# atmega8_bk.net
KiCad netlist of a schematic drawn in EAGLE
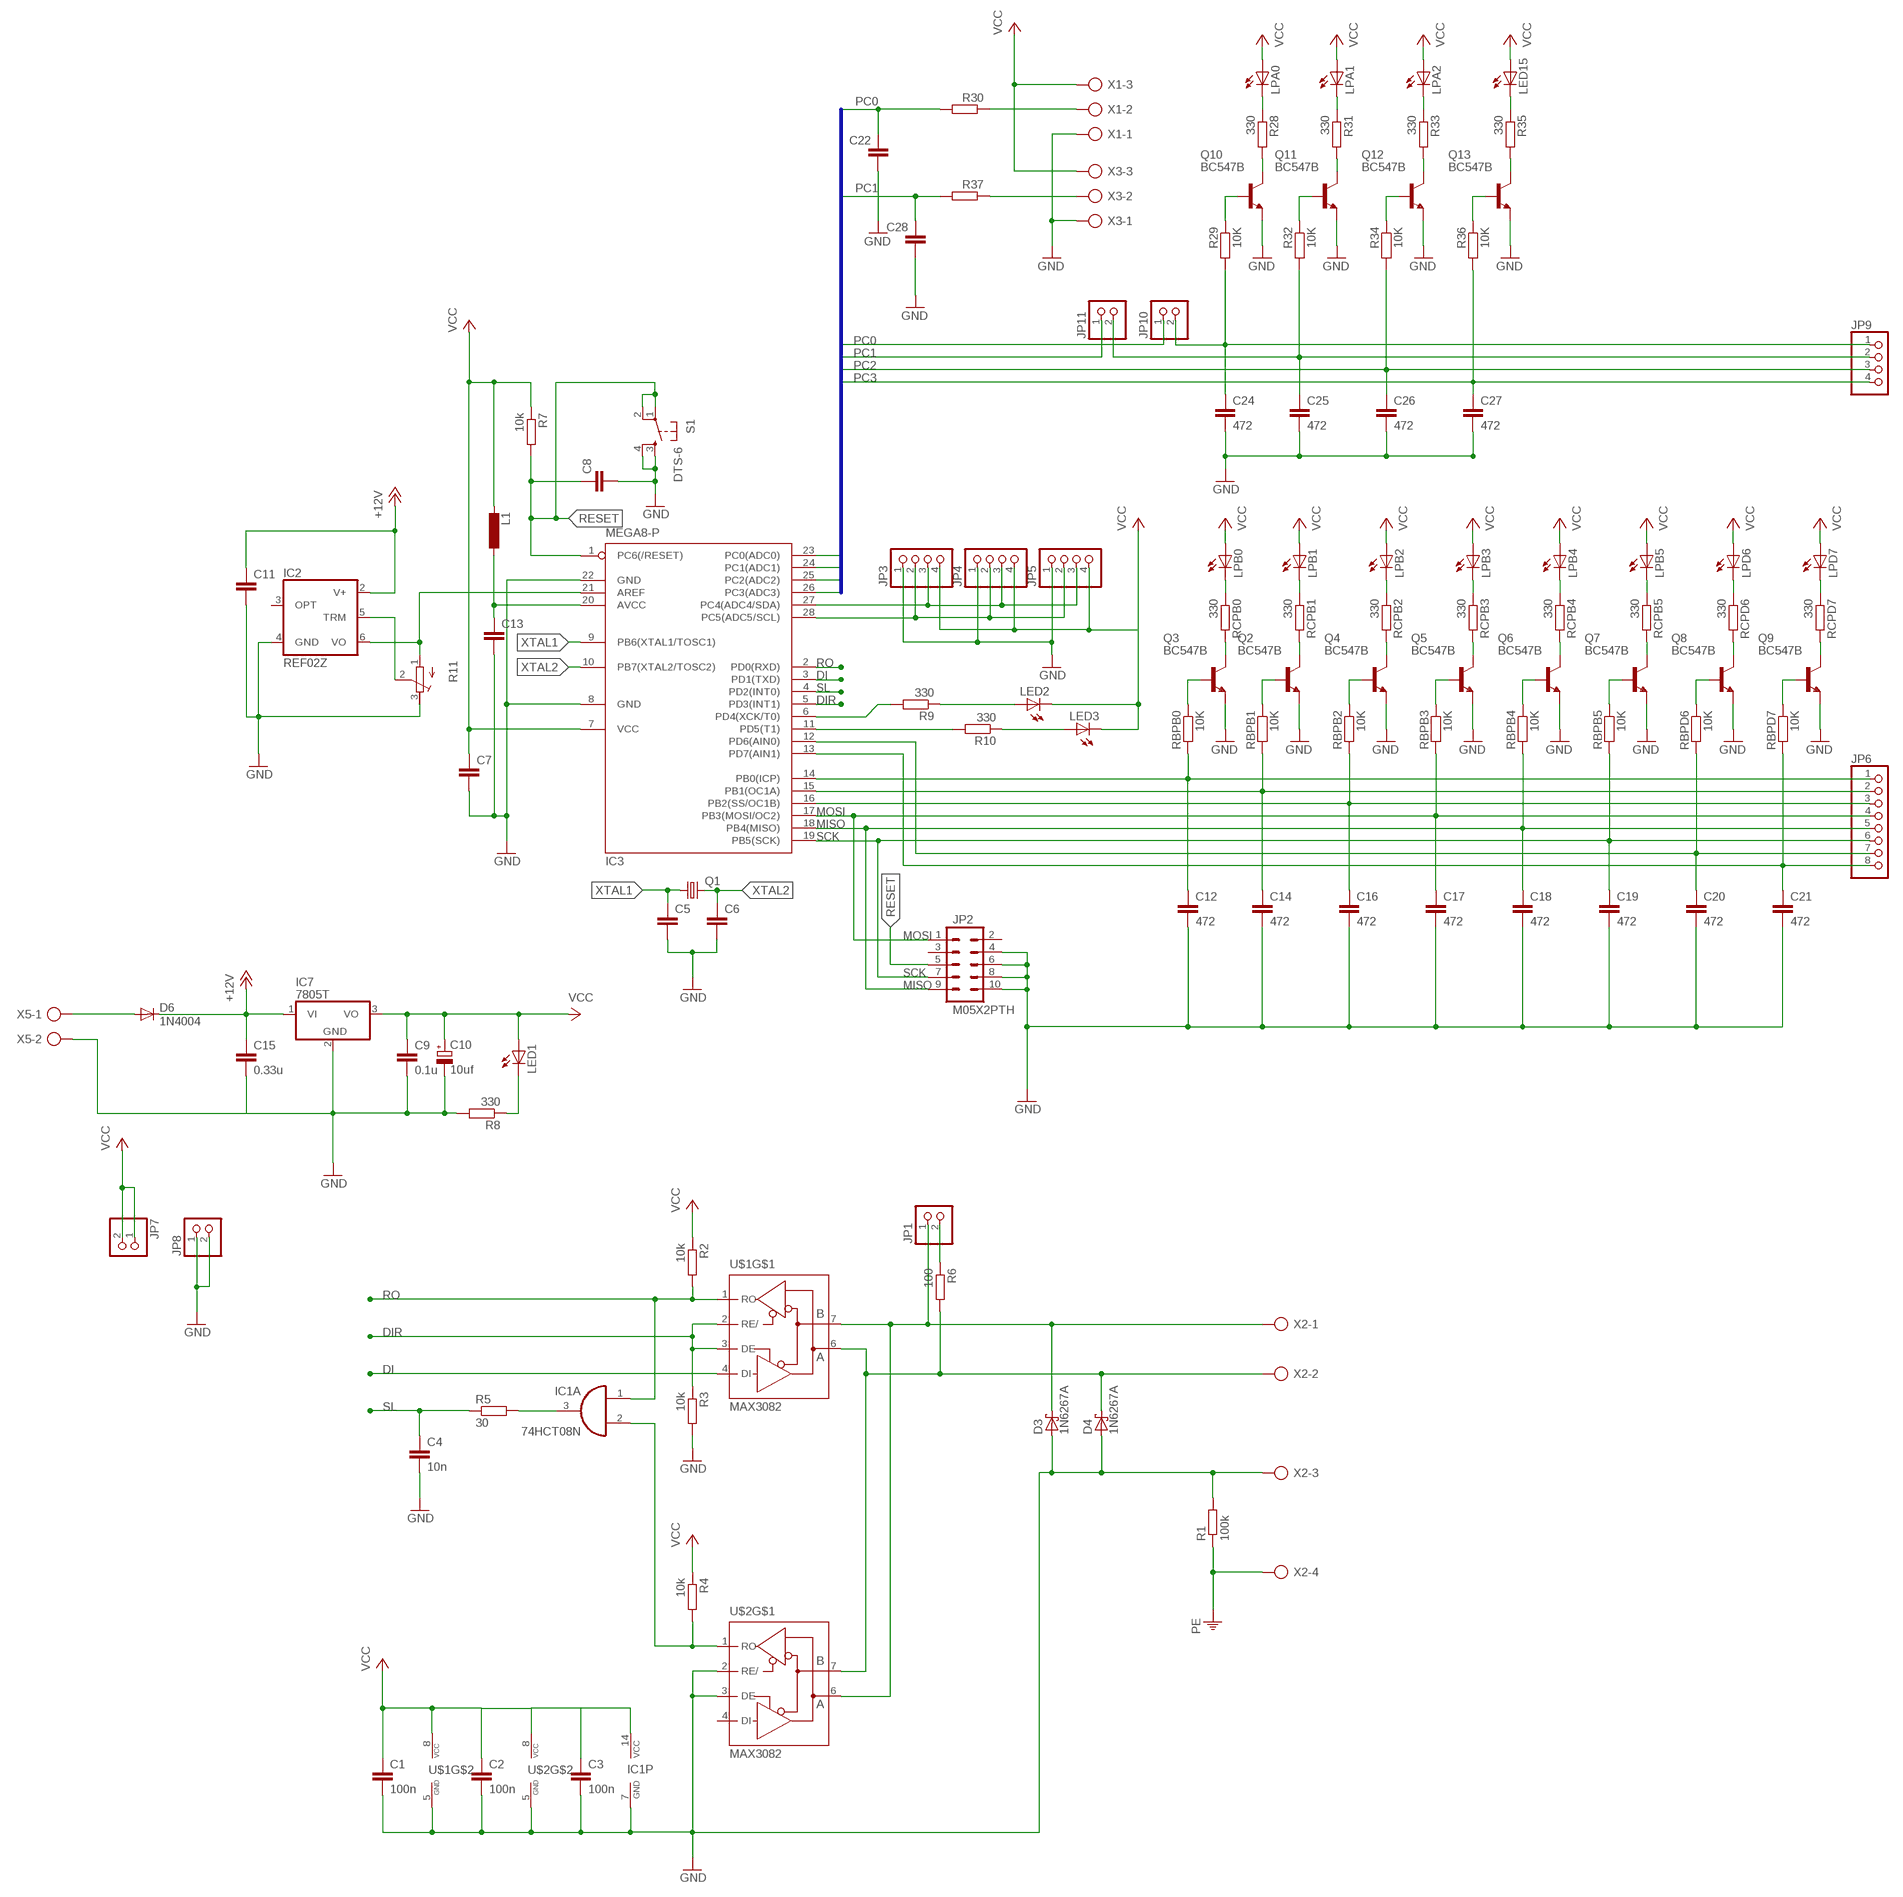
[diagram p0: schematic, sheet 1]

(export (version "E")
  (design (tool "Eeschema 10.0.6"))
  (components
    (comp (ref "C1")
      (value "100n")
      (footprint "eagle-import:C050-035X075")
      (libsource (lib "eagle-import") (part "C-EU050-035X075"))
    )
    (comp (ref "C2")
      (value "100n")
      (footprint "eagle-import:C050-035X075")
      (libsource (lib "eagle-import") (part "C-EU050-035X075"))
    )
    (comp (ref "C3")
      (value "100n")
      (footprint "eagle-import:C050-035X075")
      (libsource (lib "eagle-import") (part "C-EU050-035X075"))
    )
    (comp (ref "C4")
      (value "10n")
      (footprint "eagle-import:C050-035X075")
      (libsource (lib "eagle-import") (part "C-EU050-035X075"))
    )
    (comp (ref "C5")
      (value "C-EU050-024X044")
      (footprint "eagle-import:C050-024X044")
      (libsource (lib "eagle-import") (part "C-EU050-024X044"))
    )
    (comp (ref "C6")
      (value "C-EU050-024X044")
      (footprint "eagle-import:C050-024X044")
      (libsource (lib "eagle-import") (part "C-EU050-024X044"))
    )
    (comp (ref "C7")
      (value "C-EU050-025X075")
      (footprint "eagle-import:C050-025X075")
      (libsource (lib "eagle-import") (part "C-EU050-025X075"))
    )
    (comp (ref "C8")
      (value "C-EU050-025X075")
      (footprint "eagle-import:C050-025X075")
      (libsource (lib "eagle-import") (part "C-EU050-025X075"))
    )
    (comp (ref "C9")
      (value "0.1u")
      (footprint "eagle-import:C025-024X044")
      (libsource (lib "eagle-import") (part "C-EU025-024X044"))
    )
    (comp (ref "C10")
      (value "10uf")
      (footprint "eagle-import:E2-4")
      (libsource (lib "eagle-import") (part "CPOL-EUE2-4"))
    )
    (comp (ref "C11")
      (value "C-EU050-025X075")
      (footprint "eagle-import:C050-025X075")
      (libsource (lib "eagle-import") (part "C-EU050-025X075"))
    )
    (comp (ref "C12")
      (value "472")
      (footprint "eagle-import:C050-024X044")
      (libsource (lib "eagle-import") (part "C-EU050-024X044"))
    )
    (comp (ref "C13")
      (value "C-EU050-025X075")
      (footprint "eagle-import:C050-025X075")
      (libsource (lib "eagle-import") (part "C-EU050-025X075"))
    )
    (comp (ref "C14")
      (value "472")
      (footprint "eagle-import:C050-024X044")
      (libsource (lib "eagle-import") (part "C-EU050-024X044"))
    )
    (comp (ref "C15")
      (value "0.33u")
      (footprint "eagle-import:C025-024X044")
      (libsource (lib "eagle-import") (part "C-EU025-024X044"))
    )
    (comp (ref "C16")
      (value "472")
      (footprint "eagle-import:C050-024X044")
      (libsource (lib "eagle-import") (part "C-EU050-024X044"))
    )
    (comp (ref "C17")
      (value "472")
      (footprint "eagle-import:C050-024X044")
      (libsource (lib "eagle-import") (part "C-EU050-024X044"))
    )
    (comp (ref "C18")
      (value "472")
      (footprint "eagle-import:C050-024X044")
      (libsource (lib "eagle-import") (part "C-EU050-024X044"))
    )
    (comp (ref "C19")
      (value "472")
      (footprint "eagle-import:C050-024X044")
      (libsource (lib "eagle-import") (part "C-EU050-024X044"))
    )
    (comp (ref "C20")
      (value "472")
      (footprint "eagle-import:C050-024X044")
      (libsource (lib "eagle-import") (part "C-EU050-024X044"))
    )
    (comp (ref "C21")
      (value "472")
      (footprint "eagle-import:C050-024X044")
      (libsource (lib "eagle-import") (part "C-EU050-024X044"))
    )
    (comp (ref "C22")
      (value "C-EU050-025X075")
      (footprint "eagle-import:C050-025X075")
      (libsource (lib "eagle-import") (part "C-EU050-025X075"))
    )
    (comp (ref "C24")
      (value "472")
      (footprint "eagle-import:C050-024X044")
      (libsource (lib "eagle-import") (part "C-EU050-024X044"))
    )
    (comp (ref "C25")
      (value "472")
      (footprint "eagle-import:C050-024X044")
      (libsource (lib "eagle-import") (part "C-EU050-024X044"))
    )
    (comp (ref "C26")
      (value "472")
      (footprint "eagle-import:C050-024X044")
      (libsource (lib "eagle-import") (part "C-EU050-024X044"))
    )
    (comp (ref "C27")
      (value "472")
      (footprint "eagle-import:C050-024X044")
      (libsource (lib "eagle-import") (part "C-EU050-024X044"))
    )
    (comp (ref "C28")
      (value "C-EU050-025X075")
      (footprint "eagle-import:C050-025X075")
      (libsource (lib "eagle-import") (part "C-EU050-025X075"))
    )
    (comp (ref "D3")
      (value "1N6267A")
      (footprint "eagle-import:C4111-15")
      (libsource (lib "eagle-import") (part "1N6267A"))
    )
    (comp (ref "D4")
      (value "1N6267A")
      (footprint "eagle-import:C4111-15")
      (libsource (lib "eagle-import") (part "1N6267A"))
    )
    (comp (ref "D6")
      (value "1N4004")
      (footprint "eagle-import:DO41-10")
      (libsource (lib "eagle-import") (part "1N4004"))
    )
    (comp (ref "IC1")
      (value "74HCT08N")
      (footprint "eagle-import:DIL14")
      (libsource (lib "eagle-import") (part "7408NHCT"))
    )
    (comp (ref "IC2")
      (value "REF02Z")
      (footprint "eagle-import:DIL08")
      (libsource (lib "eagle-import") (part "REF02Z"))
    )
    (comp (ref "IC3")
      (value "MEGA8-P")
      (footprint "eagle-import:DIL28-3")
      (libsource (lib "eagle-import") (part "MEGA8-P"))
    )
    (comp (ref "IC7")
      (value "7805T")
      (footprint "eagle-import:TO220H")
      (libsource (lib "eagle-import") (part "78T05"))
    )
    (comp (ref "JP1")
      (value "PINHD-1X2")
      (footprint "eagle-import:1X02")
      (libsource (lib "eagle-import") (part "PINHD-1X2"))
    )
    (comp (ref "JP2")
      (value "M05X2PTH")
      (footprint "eagle-import:AVR_ICSP")
      (libsource (lib "eagle-import") (part "M05X2PTH"))
    )
    (comp (ref "JP3")
      (value "PINHD-1X4")
      (footprint "eagle-import:1X04")
      (libsource (lib "eagle-import") (part "PINHD-1X4"))
    )
    (comp (ref "JP4")
      (value "PINHD-1X4")
      (footprint "eagle-import:1X04")
      (libsource (lib "eagle-import") (part "PINHD-1X4"))
    )
    (comp (ref "JP5")
      (value "PINHD-1X4")
      (footprint "eagle-import:1X04")
      (libsource (lib "eagle-import") (part "PINHD-1X4"))
    )
    (comp (ref "JP6")
      (value "PINHD-1X8")
      (footprint "eagle-import:1X08")
      (libsource (lib "eagle-import") (part "PINHD-1X8"))
    )
    (comp (ref "JP7")
      (value "PINHD-1X2")
      (footprint "eagle-import:1X02")
      (libsource (lib "eagle-import") (part "PINHD-1X2"))
    )
    (comp (ref "JP8")
      (value "PINHD-1X2")
      (footprint "eagle-import:1X02")
      (libsource (lib "eagle-import") (part "PINHD-1X2"))
    )
    (comp (ref "JP9")
      (value "PINHD-1X4")
      (footprint "eagle-import:1X04")
      (libsource (lib "eagle-import") (part "PINHD-1X4"))
    )
    (comp (ref "JP10")
      (value "PINHD-1X2")
      (footprint "eagle-import:1X02")
      (libsource (lib "eagle-import") (part "PINHD-1X2"))
    )
    (comp (ref "JP11")
      (value "PINHD-1X2")
      (footprint "eagle-import:1X02")
      (libsource (lib "eagle-import") (part "PINHD-1X2"))
    )
    (comp (ref "L1")
      (value "L-EU0207/12")
      (footprint "eagle-import:0207_12")
      (libsource (lib "eagle-import") (part "L-EU0207/12"))
    )
    (comp (ref "LED1")
      (value "LED3MM")
      (footprint "eagle-import:LED3MM")
      (libsource (lib "eagle-import") (part "LED3MM"))
    )
    (comp (ref "LED2")
      (value "LED3MM")
      (footprint "eagle-import:LED3MM")
      (libsource (lib "eagle-import") (part "LED3MM"))
    )
    (comp (ref "LED3")
      (value "LED3MM")
      (footprint "eagle-import:LED3MM")
      (libsource (lib "eagle-import") (part "LED3MM"))
    )
    (comp (ref "LED15")
      (value "LED3MM")
      (footprint "eagle-import:LED3MM")
      (libsource (lib "eagle-import") (part "LED3MM"))
    )
    (comp (ref "LPA0")
      (value "LED3MM")
      (footprint "eagle-import:LED3MM")
      (libsource (lib "eagle-import") (part "LED3MM"))
    )
    (comp (ref "LPA1")
      (value "LED3MM")
      (footprint "eagle-import:LED3MM")
      (libsource (lib "eagle-import") (part "LED3MM"))
    )
    (comp (ref "LPA2")
      (value "LED3MM")
      (footprint "eagle-import:LED3MM")
      (libsource (lib "eagle-import") (part "LED3MM"))
    )
    (comp (ref "LPB0")
      (value "LED3MM")
      (footprint "eagle-import:LED3MM")
      (libsource (lib "eagle-import") (part "LED3MM"))
    )
    (comp (ref "LPB1")
      (value "LED3MM")
      (footprint "eagle-import:LED3MM")
      (libsource (lib "eagle-import") (part "LED3MM"))
    )
    (comp (ref "LPB2")
      (value "LED3MM")
      (footprint "eagle-import:LED3MM")
      (libsource (lib "eagle-import") (part "LED3MM"))
    )
    (comp (ref "LPB3")
      (value "LED3MM")
      (footprint "eagle-import:LED3MM")
      (libsource (lib "eagle-import") (part "LED3MM"))
    )
    (comp (ref "LPB4")
      (value "LED3MM")
      (footprint "eagle-import:LED3MM")
      (libsource (lib "eagle-import") (part "LED3MM"))
    )
    (comp (ref "LPB5")
      (value "LED3MM")
      (footprint "eagle-import:LED3MM")
      (libsource (lib "eagle-import") (part "LED3MM"))
    )
    (comp (ref "LPD6")
      (value "LED3MM")
      (footprint "eagle-import:LED3MM")
      (libsource (lib "eagle-import") (part "LED3MM"))
    )
    (comp (ref "LPD7")
      (value "LED3MM")
      (footprint "eagle-import:LED3MM")
      (libsource (lib "eagle-import") (part "LED3MM"))
    )
    (comp (ref "Q1")
      (value "CRYSTALHC49U70")
      (footprint "eagle-import:HC49U70")
      (libsource (lib "eagle-import") (part "CRYSTALHC49U70"))
    )
    (comp (ref "Q2")
      (value "BC547B")
      (footprint "eagle-import:TO92")
      (libsource (lib "eagle-import") (part "BC547B"))
    )
    (comp (ref "Q3")
      (value "BC547B")
      (footprint "eagle-import:TO92")
      (libsource (lib "eagle-import") (part "BC547B"))
    )
    (comp (ref "Q4")
      (value "BC547B")
      (footprint "eagle-import:TO92")
      (libsource (lib "eagle-import") (part "BC547B"))
    )
    (comp (ref "Q5")
      (value "BC547B")
      (footprint "eagle-import:TO92")
      (libsource (lib "eagle-import") (part "BC547B"))
    )
    (comp (ref "Q6")
      (value "BC547B")
      (footprint "eagle-import:TO92")
      (libsource (lib "eagle-import") (part "BC547B"))
    )
    (comp (ref "Q7")
      (value "BC547B")
      (footprint "eagle-import:TO92")
      (libsource (lib "eagle-import") (part "BC547B"))
    )
    (comp (ref "Q8")
      (value "BC547B")
      (footprint "eagle-import:TO92")
      (libsource (lib "eagle-import") (part "BC547B"))
    )
    (comp (ref "Q9")
      (value "BC547B")
      (footprint "eagle-import:TO92")
      (libsource (lib "eagle-import") (part "BC547B"))
    )
    (comp (ref "Q10")
      (value "BC547B")
      (footprint "eagle-import:TO92")
      (libsource (lib "eagle-import") (part "BC547B"))
    )
    (comp (ref "Q11")
      (value "BC547B")
      (footprint "eagle-import:TO92")
      (libsource (lib "eagle-import") (part "BC547B"))
    )
    (comp (ref "Q12")
      (value "BC547B")
      (footprint "eagle-import:TO92")
      (libsource (lib "eagle-import") (part "BC547B"))
    )
    (comp (ref "Q13")
      (value "BC547B")
      (footprint "eagle-import:TO92")
      (libsource (lib "eagle-import") (part "BC547B"))
    )
    (comp (ref "R1")
      (value "100k")
      (footprint "eagle-import:0204_7")
      (libsource (lib "eagle-import") (part "resistor_R-EU_0204/7"))
    )
    (comp (ref "R2")
      (value "10k")
      (footprint "eagle-import:0204_7")
      (libsource (lib "eagle-import") (part "resistor_R-EU_0204/7"))
    )
    (comp (ref "R3")
      (value "10k")
      (footprint "eagle-import:0204_7")
      (libsource (lib "eagle-import") (part "resistor_R-EU_0204/7"))
    )
    (comp (ref "R4")
      (value "10k")
      (footprint "eagle-import:0204_7")
      (libsource (lib "eagle-import") (part "resistor_R-EU_0204/7"))
    )
    (comp (ref "R5")
      (value "30")
      (footprint "eagle-import:0207_10")
      (libsource (lib "eagle-import") (part "R-EU_0207/10"))
    )
    (comp (ref "R6")
      (value "100")
      (footprint "eagle-import:0204_7")
      (libsource (lib "eagle-import") (part "resistor_R-EU_0204/7"))
    )
    (comp (ref "R7")
      (value "10k")
      (footprint "eagle-import:0204_7")
      (libsource (lib "eagle-import") (part "R-EU_0204/7"))
    )
    (comp (ref "R8")
      (value "330")
      (footprint "eagle-import:0204_7")
      (libsource (lib "eagle-import") (part "R-EU_0204/7"))
    )
    (comp (ref "R9")
      (value "330")
      (footprint "eagle-import:0204_7")
      (libsource (lib "eagle-import") (part "R-EU_0204/7"))
    )
    (comp (ref "R10")
      (value "330")
      (footprint "eagle-import:0204_7")
      (libsource (lib "eagle-import") (part "R-EU_0204/7"))
    )
    (comp (ref "R11")
      (value "R-TRIMM64W")
      (footprint "eagle-import:RTRIM64W")
      (libsource (lib "eagle-import") (part "R-TRIMM64W"))
    )
    (comp (ref "R28")
      (value "330")
      (footprint "eagle-import:0204_7")
      (libsource (lib "eagle-import") (part "R-EU_0204/7"))
    )
    (comp (ref "R29")
      (value "10K")
      (footprint "eagle-import:0204_7")
      (libsource (lib "eagle-import") (part "R-EU_0204/7"))
    )
    (comp (ref "R30")
      (value "R-EU_0204/7")
      (footprint "eagle-import:0204_7")
      (libsource (lib "eagle-import") (part "R-EU_0204/7"))
    )
    (comp (ref "R31")
      (value "330")
      (footprint "eagle-import:0204_7")
      (libsource (lib "eagle-import") (part "R-EU_0204/7"))
    )
    (comp (ref "R32")
      (value "10K")
      (footprint "eagle-import:0204_7")
      (libsource (lib "eagle-import") (part "R-EU_0204/7"))
    )
    (comp (ref "R33")
      (value "330")
      (footprint "eagle-import:0204_7")
      (libsource (lib "eagle-import") (part "R-EU_0204/7"))
    )
    (comp (ref "R34")
      (value "10K")
      (footprint "eagle-import:0204_7")
      (libsource (lib "eagle-import") (part "R-EU_0204/7"))
    )
    (comp (ref "R35")
      (value "330")
      (footprint "eagle-import:0204_7")
      (libsource (lib "eagle-import") (part "R-EU_0204/7"))
    )
    (comp (ref "R36")
      (value "10K")
      (footprint "eagle-import:0204_7")
      (libsource (lib "eagle-import") (part "R-EU_0204/7"))
    )
    (comp (ref "R37")
      (value "R-EU_0204/7")
      (footprint "eagle-import:0204_7")
      (libsource (lib "eagle-import") (part "R-EU_0204/7"))
    )
    (comp (ref "RBPB0")
      (value "10K")
      (footprint "eagle-import:0204_7")
      (libsource (lib "eagle-import") (part "R-EU_0204/7"))
    )
    (comp (ref "RBPB1")
      (value "10K")
      (footprint "eagle-import:0204_7")
      (libsource (lib "eagle-import") (part "R-EU_0204/7"))
    )
    (comp (ref "RBPB2")
      (value "10K")
      (footprint "eagle-import:0204_7")
      (libsource (lib "eagle-import") (part "R-EU_0204/7"))
    )
    (comp (ref "RBPB3")
      (value "10K")
      (footprint "eagle-import:0204_7")
      (libsource (lib "eagle-import") (part "R-EU_0204/7"))
    )
    (comp (ref "RBPB4")
      (value "10K")
      (footprint "eagle-import:0204_7")
      (libsource (lib "eagle-import") (part "R-EU_0204/7"))
    )
    (comp (ref "RBPB5")
      (value "10K")
      (footprint "eagle-import:0204_7")
      (libsource (lib "eagle-import") (part "R-EU_0204/7"))
    )
    (comp (ref "RBPD6")
      (value "10K")
      (footprint "eagle-import:0204_7")
      (libsource (lib "eagle-import") (part "R-EU_0204/7"))
    )
    (comp (ref "RBPD7")
      (value "10K")
      (footprint "eagle-import:0204_7")
      (libsource (lib "eagle-import") (part "R-EU_0204/7"))
    )
    (comp (ref "RCPB0")
      (value "330")
      (footprint "eagle-import:0204_7")
      (libsource (lib "eagle-import") (part "R-EU_0204/7"))
    )
    (comp (ref "RCPB1")
      (value "330")
      (footprint "eagle-import:0204_7")
      (libsource (lib "eagle-import") (part "R-EU_0204/7"))
    )
    (comp (ref "RCPB2")
      (value "330")
      (footprint "eagle-import:0204_7")
      (libsource (lib "eagle-import") (part "R-EU_0204/7"))
    )
    (comp (ref "RCPB3")
      (value "330")
      (footprint "eagle-import:0204_7")
      (libsource (lib "eagle-import") (part "R-EU_0204/7"))
    )
    (comp (ref "RCPB4")
      (value "330")
      (footprint "eagle-import:0204_7")
      (libsource (lib "eagle-import") (part "R-EU_0204/7"))
    )
    (comp (ref "RCPB5")
      (value "330")
      (footprint "eagle-import:0204_7")
      (libsource (lib "eagle-import") (part "R-EU_0204/7"))
    )
    (comp (ref "RCPD6")
      (value "330")
      (footprint "eagle-import:0204_7")
      (libsource (lib "eagle-import") (part "R-EU_0204/7"))
    )
    (comp (ref "RCPD7")
      (value "330")
      (footprint "eagle-import:0204_7")
      (libsource (lib "eagle-import") (part "R-EU_0204/7"))
    )
    (comp (ref "S1")
      (value "DTS-6")
      (footprint "eagle-import:DTS-6")
      (libsource (lib "eagle-import") (part "DTS-6"))
    )
    (comp (ref "U$1")
      (value "MAX3082")
      (footprint "eagle-import:DIL08")
      (libsource (lib "eagle-import") (part "MAX3082"))
    )
    (comp (ref "U$2")
      (value "MAX3082")
      (footprint "eagle-import:DIL08")
      (libsource (lib "eagle-import") (part "MAX3082"))
    )
    (comp (ref "X1")
      (value "AK500/3")
      (footprint "eagle-import:AK500_3")
      (libsource (lib "eagle-import") (part "AK500/3"))
    )
    (comp (ref "X2")
      (value "AK500/4")
      (footprint "eagle-import:AK500_4")
      (libsource (lib "eagle-import") (part "AK500/4"))
    )
    (comp (ref "X3")
      (value "AK500/3")
      (footprint "eagle-import:AK500_3")
      (libsource (lib "eagle-import") (part "AK500/3"))
    )
    (comp (ref "X5")
      (value "AK500/2")
      (footprint "eagle-import:AK500_2")
      (libsource (lib "eagle-import") (part "AK500/2"))
    )
  )
  (nets
    (net (code "1") (name "+12V") (class "Default")
      (node (ref "C11") (pin "1") (pinfunction "1_1") (pintype "passive"))
      (node (ref "C15") (pin "1") (pinfunction "1_1") (pintype "passive"))
      (node (ref "D6") (pin "C") (pinfunction "C_C") (pintype "passive"))
      (node (ref "IC2") (pin "2") (pinfunction "V+_2") (pintype "power_in"))
      (node (ref "IC7") (pin "1") (pinfunction "VI_1") (pintype "input"))
    )
    (net (code "2") (name "/DI") (class "Default")
      (node (ref "IC3") (pin "3") (pinfunction "PD1(TXD)_3") (pintype "bidirectional"))
      (node (ref "U$1") (pin "4") (pinfunction "DI_4") (pintype "input"))
    )
    (net (code "3") (name "/DIR") (class "Default")
      (node (ref "IC3") (pin "5") (pinfunction "PD3(INT1)_5") (pintype "bidirectional"))
      (node (ref "R3") (pin "1") (pinfunction "1_1") (pintype "passive"))
      (node (ref "U$1") (pin "2") (pinfunction "RE/_2") (pintype "input"))
      (node (ref "U$1") (pin "3") (pinfunction "DE_3") (pintype "input"))
    )
    (net (code "4") (name "/MISO") (class "Default")
      (node (ref "C18") (pin "1") (pinfunction "1_1") (pintype "passive"))
      (node (ref "IC3") (pin "18") (pinfunction "PB4(MISO)_18") (pintype "bidirectional"))
      (node (ref "JP2") (pin "9") (pinfunction "9_9") (pintype "passive"))
      (node (ref "JP6") (pin "5") (pinfunction "5_5") (pintype "passive"))
      (node (ref "RBPB4") (pin "2") (pinfunction "2_2") (pintype "passive"))
    )
    (net (code "5") (name "/MOSI") (class "Default")
      (node (ref "C17") (pin "1") (pinfunction "1_1") (pintype "passive"))
      (node (ref "IC3") (pin "17") (pinfunction "PB3(MOSI/OC2)_17") (pintype "bidirectional"))
      (node (ref "JP2") (pin "1") (pinfunction "1_1") (pintype "passive"))
      (node (ref "JP6") (pin "4") (pinfunction "4_4") (pintype "passive"))
      (node (ref "RBPB3") (pin "2") (pinfunction "2_2") (pintype "passive"))
    )
    (net (code "6") (name "/PC0") (class "Default")
      (node (ref "C22") (pin "1") (pinfunction "1_1") (pintype "passive"))
      (node (ref "IC3") (pin "23") (pinfunction "PC0(ADC0)_23") (pintype "bidirectional"))
      (node (ref "JP10") (pin "1") (pinfunction "1_1") (pintype "passive"))
      (node (ref "R30") (pin "2") (pinfunction "2_2") (pintype "passive"))
    )
    (net (code "7") (name "/PC1") (class "Default")
      (node (ref "C28") (pin "1") (pinfunction "1_1") (pintype "passive"))
      (node (ref "IC3") (pin "24") (pinfunction "PC1(ADC1)_24") (pintype "bidirectional"))
      (node (ref "JP11") (pin "1") (pinfunction "1_1") (pintype "passive"))
      (node (ref "R37") (pin "2") (pinfunction "2_2") (pintype "passive"))
    )
    (net (code "8") (name "/PC2") (class "Default")
      (node (ref "C26") (pin "1") (pinfunction "1_1") (pintype "passive"))
      (node (ref "IC3") (pin "25") (pinfunction "PC2(ADC2)_25") (pintype "bidirectional"))
      (node (ref "JP9") (pin "3") (pinfunction "3_3") (pintype "passive"))
      (node (ref "R34") (pin "2") (pinfunction "2_2") (pintype "passive"))
    )
    (net (code "9") (name "/PC3") (class "Default")
      (node (ref "C27") (pin "1") (pinfunction "1_1") (pintype "passive"))
      (node (ref "IC3") (pin "26") (pinfunction "PC3(ADC3)_26") (pintype "bidirectional"))
      (node (ref "JP9") (pin "4") (pinfunction "4_4") (pintype "passive"))
      (node (ref "R36") (pin "2") (pinfunction "2_2") (pintype "passive"))
    )
    (net (code "10") (name "/RO") (class "Default")
      (node (ref "IC1") (pin "1") (pinfunction "I0_1") (pintype "input"))
      (node (ref "IC3") (pin "2") (pinfunction "PD0(RXD)_2") (pintype "bidirectional"))
      (node (ref "R2") (pin "2") (pinfunction "2_2") (pintype "passive"))
      (node (ref "U$1") (pin "1") (pinfunction "RO_1") (pintype "output"))
    )
    (net (code "11") (name "/SCK") (class "Default")
      (node (ref "C19") (pin "1") (pinfunction "1_1") (pintype "passive"))
      (node (ref "IC3") (pin "19") (pinfunction "PB5(SCK)_19") (pintype "bidirectional"))
      (node (ref "JP2") (pin "7") (pinfunction "7_7") (pintype "passive"))
      (node (ref "JP6") (pin "6") (pinfunction "6_6") (pintype "passive"))
      (node (ref "RBPB5") (pin "2") (pinfunction "2_2") (pintype "passive"))
    )
    (net (code "12") (name "/SL") (class "Default")
      (node (ref "C4") (pin "1") (pinfunction "1_1") (pintype "passive"))
      (node (ref "IC3") (pin "4") (pinfunction "PD2(INT0)_4") (pintype "bidirectional"))
      (node (ref "R5") (pin "1") (pinfunction "1_1") (pintype "passive"))
    )
    (net (code "13") (name "GND") (class "Default")
      (node (ref "C1") (pin "2") (pinfunction "2_2") (pintype "passive"))
      (node (ref "C10") (pin "-") (pinfunction "-_-") (pintype "passive"))
      (node (ref "C11") (pin "2") (pinfunction "2_2") (pintype "passive"))
      (node (ref "C12") (pin "2") (pinfunction "2_2") (pintype "passive"))
      (node (ref "C13") (pin "2") (pinfunction "2_2") (pintype "passive"))
      (node (ref "C14") (pin "2") (pinfunction "2_2") (pintype "passive"))
      (node (ref "C15") (pin "2") (pinfunction "2_2") (pintype "passive"))
      (node (ref "C16") (pin "2") (pinfunction "2_2") (pintype "passive"))
      (node (ref "C17") (pin "2") (pinfunction "2_2") (pintype "passive"))
      (node (ref "C18") (pin "2") (pinfunction "2_2") (pintype "passive"))
      (node (ref "C19") (pin "2") (pinfunction "2_2") (pintype "passive"))
      (node (ref "C2") (pin "2") (pinfunction "2_2") (pintype "passive"))
      (node (ref "C20") (pin "2") (pinfunction "2_2") (pintype "passive"))
      (node (ref "C21") (pin "2") (pinfunction "2_2") (pintype "passive"))
      (node (ref "C22") (pin "2") (pinfunction "2_2") (pintype "passive"))
      (node (ref "C24") (pin "2") (pinfunction "2_2") (pintype "passive"))
      (node (ref "C25") (pin "2") (pinfunction "2_2") (pintype "passive"))
      (node (ref "C26") (pin "2") (pinfunction "2_2") (pintype "passive"))
      (node (ref "C27") (pin "2") (pinfunction "2_2") (pintype "passive"))
      (node (ref "C28") (pin "2") (pinfunction "2_2") (pintype "passive"))
      (node (ref "C3") (pin "2") (pinfunction "2_2") (pintype "passive"))
      (node (ref "C4") (pin "2") (pinfunction "2_2") (pintype "passive"))
      (node (ref "C5") (pin "2") (pinfunction "2_2") (pintype "passive"))
      (node (ref "C6") (pin "2") (pinfunction "2_2") (pintype "passive"))
      (node (ref "C7") (pin "2") (pinfunction "2_2") (pintype "passive"))
      (node (ref "C8") (pin "2") (pinfunction "2_2") (pintype "passive"))
      (node (ref "C9") (pin "2") (pinfunction "2_2") (pintype "passive"))
      (node (ref "D3") (pin "A") (pinfunction "A_A") (pintype "passive"))
      (node (ref "D4") (pin "A") (pinfunction "A_A") (pintype "passive"))
      (node (ref "IC1") (pin "7") (pinfunction "GND_7") (pintype "power_in"))
      (node (ref "IC2") (pin "4") (pinfunction "GND_4") (pintype "power_in"))
      (node (ref "IC3") (pin "22") (pinfunction "GND_22") (pintype "power_in"))
      (node (ref "IC3") (pin "8") (pinfunction "GND_8") (pintype "power_in"))
      (node (ref "IC7") (pin "2") (pinfunction "GND_2") (pintype "passive"))
      (node (ref "JP2") (pin "10") (pinfunction "10_10") (pintype "passive"))
      (node (ref "JP2") (pin "4") (pinfunction "4_4") (pintype "passive"))
      (node (ref "JP2") (pin "6") (pinfunction "6_6") (pintype "passive"))
      (node (ref "JP2") (pin "8") (pinfunction "8_8") (pintype "passive"))
      (node (ref "JP3") (pin "1") (pinfunction "1_1") (pintype "passive"))
      (node (ref "JP4") (pin "1") (pinfunction "1_1") (pintype "passive"))
      (node (ref "JP5") (pin "1") (pinfunction "1_1") (pintype "passive"))
      (node (ref "JP8") (pin "1") (pinfunction "1_1") (pintype "passive"))
      (node (ref "JP8") (pin "2") (pinfunction "2_2") (pintype "passive"))
      (node (ref "Q10") (pin "1") (pinfunction "E_1") (pintype "passive"))
      (node (ref "Q11") (pin "1") (pinfunction "E_1") (pintype "passive"))
      (node (ref "Q12") (pin "1") (pinfunction "E_1") (pintype "passive"))
      (node (ref "Q13") (pin "1") (pinfunction "E_1") (pintype "passive"))
      (node (ref "Q2") (pin "1") (pinfunction "E_1") (pintype "passive"))
      (node (ref "Q3") (pin "1") (pinfunction "E_1") (pintype "passive"))
      (node (ref "Q4") (pin "1") (pinfunction "E_1") (pintype "passive"))
      (node (ref "Q5") (pin "1") (pinfunction "E_1") (pintype "passive"))
      (node (ref "Q6") (pin "1") (pinfunction "E_1") (pintype "passive"))
      (node (ref "Q7") (pin "1") (pinfunction "E_1") (pintype "passive"))
      (node (ref "Q8") (pin "1") (pinfunction "E_1") (pintype "passive"))
      (node (ref "Q9") (pin "1") (pinfunction "E_1") (pintype "passive"))
      (node (ref "R1") (pin "2") (pinfunction "2_2") (pintype "passive"))
      (node (ref "R11") (pin "3") (pinfunction "E_3") (pintype "passive"))
      (node (ref "R3") (pin "2") (pinfunction "2_2") (pintype "passive"))
      (node (ref "R8") (pin "2") (pinfunction "2_2") (pintype "passive"))
      (node (ref "S1") (pin "3") (pinfunction "3_3") (pintype "passive"))
      (node (ref "S1") (pin "4") (pinfunction "4_4") (pintype "passive"))
      (node (ref "U$1") (pin "5") (pinfunction "GND_5") (pintype "power_in"))
      (node (ref "U$2") (pin "2") (pinfunction "RE/_2") (pintype "input"))
      (node (ref "U$2") (pin "3") (pinfunction "DE_3") (pintype "input"))
      (node (ref "U$2") (pin "5") (pinfunction "GND_5") (pintype "power_in"))
      (node (ref "X1") (pin "1") (pinfunction "KL_1") (pintype "passive"))
      (node (ref "X2") (pin "3") (pinfunction "KL_3") (pintype "passive"))
      (node (ref "X3") (pin "1") (pinfunction "KL_1") (pintype "passive"))
      (node (ref "X5") (pin "2") (pinfunction "KL_2") (pintype "passive"))
    )
    (net (code "14") (name "Net-(C24-Pad1)") (class "Default")
      (node (ref "C24") (pin "1") (pinfunction "1_1") (pintype "passive"))
      (node (ref "JP10") (pin "2") (pinfunction "2_2") (pintype "passive"))
      (node (ref "JP9") (pin "1") (pinfunction "1_1") (pintype "passive"))
      (node (ref "R29") (pin "2") (pinfunction "2_2") (pintype "passive"))
    )
    (net (code "15") (name "Net-(C25-Pad1)") (class "Default")
      (node (ref "C25") (pin "1") (pinfunction "1_1") (pintype "passive"))
      (node (ref "JP11") (pin "2") (pinfunction "2_2") (pintype "passive"))
      (node (ref "JP9") (pin "2") (pinfunction "2_2") (pintype "passive"))
      (node (ref "R32") (pin "2") (pinfunction "2_2") (pintype "passive"))
    )
    (net (code "16") (name "Net-(IC1A-I1)") (class "Default")
      (node (ref "IC1") (pin "2") (pinfunction "I1_2") (pintype "input"))
      (node (ref "R4") (pin "2") (pinfunction "2_2") (pintype "passive"))
      (node (ref "U$2") (pin "1") (pinfunction "RO_1") (pintype "output"))
    )
    (net (code "17") (name "Net-(IC1A-O)") (class "Default")
      (node (ref "IC1") (pin "3") (pinfunction "O_3") (pintype "output"))
      (node (ref "R5") (pin "2") (pinfunction "2_2") (pintype "passive"))
    )
    (net (code "18") (name "Net-(IC2-TRM)") (class "Default")
      (node (ref "IC2") (pin "5") (pinfunction "TRM_5") (pintype "input"))
      (node (ref "R11") (pin "2") (pinfunction "S_2") (pintype "passive"))
    )
    (net (code "19") (name "Net-(IC2-VO)") (class "Default")
      (node (ref "IC2") (pin "6") (pinfunction "VO_6") (pintype "output"))
      (node (ref "IC3") (pin "21") (pinfunction "AREF_21") (pintype "passive"))
      (node (ref "R11") (pin "1") (pinfunction "A_1") (pintype "passive"))
    )
    (net (code "20") (name "Net-(IC3-AVCC)") (class "Default")
      (node (ref "C13") (pin "1") (pinfunction "1_1") (pintype "passive"))
      (node (ref "IC3") (pin "20") (pinfunction "AVCC_20") (pintype "power_in"))
      (node (ref "L1") (pin "1") (pinfunction "1_1") (pintype "passive"))
    )
    (net (code "21") (name "Net-(IC3-PB0(ICP))") (class "Default")
      (node (ref "C12") (pin "1") (pinfunction "1_1") (pintype "passive"))
      (node (ref "IC3") (pin "14") (pinfunction "PB0(ICP)_14") (pintype "bidirectional"))
      (node (ref "JP6") (pin "1") (pinfunction "1_1") (pintype "passive"))
      (node (ref "RBPB0") (pin "2") (pinfunction "2_2") (pintype "passive"))
    )
    (net (code "22") (name "Net-(IC3-PB1(OC1A))") (class "Default")
      (node (ref "C14") (pin "1") (pinfunction "1_1") (pintype "passive"))
      (node (ref "IC3") (pin "15") (pinfunction "PB1(OC1A)_15") (pintype "bidirectional"))
      (node (ref "JP6") (pin "2") (pinfunction "2_2") (pintype "passive"))
      (node (ref "RBPB1") (pin "2") (pinfunction "2_2") (pintype "passive"))
    )
    (net (code "23") (name "Net-(IC3-PB2(SS{slash}OC1B))") (class "Default")
      (node (ref "C16") (pin "1") (pinfunction "1_1") (pintype "passive"))
      (node (ref "IC3") (pin "16") (pinfunction "PB2(SS/OC1B)_16") (pintype "bidirectional"))
      (node (ref "JP6") (pin "3") (pinfunction "3_3") (pintype "passive"))
      (node (ref "RBPB2") (pin "2") (pinfunction "2_2") (pintype "passive"))
    )
    (net (code "24") (name "Net-(IC3-PC4(ADC4{slash}SDA))") (class "Default")
      (node (ref "IC3") (pin "27") (pinfunction "PC4(ADC4/SDA)_27") (pintype "bidirectional"))
      (node (ref "JP3") (pin "3") (pinfunction "3_3") (pintype "passive"))
      (node (ref "JP4") (pin "3") (pinfunction "3_3") (pintype "passive"))
      (node (ref "JP5") (pin "3") (pinfunction "3_3") (pintype "passive"))
    )
    (net (code "25") (name "Net-(IC3-PC5(ADC5{slash}SCL))") (class "Default")
      (node (ref "IC3") (pin "28") (pinfunction "PC5(ADC5/SCL)_28") (pintype "bidirectional"))
      (node (ref "JP3") (pin "2") (pinfunction "2_2") (pintype "passive"))
      (node (ref "JP4") (pin "2") (pinfunction "2_2") (pintype "passive"))
      (node (ref "JP5") (pin "2") (pinfunction "2_2") (pintype "passive"))
    )
    (net (code "26") (name "Net-(IC3-PD4(XCK{slash}T0))") (class "Default")
      (node (ref "IC3") (pin "6") (pinfunction "PD4(XCK/T0)_6") (pintype "bidirectional"))
      (node (ref "R9") (pin "2") (pinfunction "2_2") (pintype "passive"))
    )
    (net (code "27") (name "Net-(IC3-PD5(T1))") (class "Default")
      (node (ref "IC3") (pin "11") (pinfunction "PD5(T1)_11") (pintype "bidirectional"))
      (node (ref "R10") (pin "2") (pinfunction "2_2") (pintype "passive"))
    )
    (net (code "28") (name "Net-(IC3-PD6(AIN0))") (class "Default")
      (node (ref "C20") (pin "1") (pinfunction "1_1") (pintype "passive"))
      (node (ref "IC3") (pin "12") (pinfunction "PD6(AIN0)_12") (pintype "bidirectional"))
      (node (ref "JP6") (pin "7") (pinfunction "7_7") (pintype "passive"))
      (node (ref "RBPD6") (pin "2") (pinfunction "2_2") (pintype "passive"))
    )
    (net (code "29") (name "Net-(IC3-PD7(AIN1))") (class "Default")
      (node (ref "C21") (pin "1") (pinfunction "1_1") (pintype "passive"))
      (node (ref "IC3") (pin "13") (pinfunction "PD7(AIN1)_13") (pintype "bidirectional"))
      (node (ref "JP6") (pin "8") (pinfunction "8_8") (pintype "passive"))
      (node (ref "RBPD7") (pin "2") (pinfunction "2_2") (pintype "passive"))
    )
    (net (code "30") (name "Net-(JP1-Pad2)") (class "Default")
      (node (ref "JP1") (pin "2") (pinfunction "2_2") (pintype "passive"))
      (node (ref "R6") (pin "1") (pinfunction "1_1") (pintype "passive"))
    )
    (net (code "31") (name "Net-(LED1-C)") (class "Default")
      (node (ref "LED1") (pin "K") (pinfunction "C_K") (pintype "passive"))
      (node (ref "R8") (pin "1") (pinfunction "1_1") (pintype "passive"))
    )
    (net (code "32") (name "Net-(LED2-PadA)") (class "Default")
      (node (ref "LED2") (pin "A") (pinfunction "A_A") (pintype "passive"))
      (node (ref "R9") (pin "1") (pinfunction "1_1") (pintype "passive"))
    )
    (net (code "33") (name "Net-(LED3-PadA)") (class "Default")
      (node (ref "LED3") (pin "A") (pinfunction "A_A") (pintype "passive"))
      (node (ref "R10") (pin "1") (pinfunction "1_1") (pintype "passive"))
    )
    (net (code "34") (name "Net-(LED15-C)") (class "Default")
      (node (ref "LED15") (pin "K") (pinfunction "C_K") (pintype "passive"))
      (node (ref "R35") (pin "1") (pinfunction "1_1") (pintype "passive"))
    )
    (net (code "35") (name "Net-(LPA0-C)") (class "Default")
      (node (ref "LPA0") (pin "K") (pinfunction "C_K") (pintype "passive"))
      (node (ref "R28") (pin "1") (pinfunction "1_1") (pintype "passive"))
    )
    (net (code "36") (name "Net-(LPA1-C)") (class "Default")
      (node (ref "LPA1") (pin "K") (pinfunction "C_K") (pintype "passive"))
      (node (ref "R31") (pin "1") (pinfunction "1_1") (pintype "passive"))
    )
    (net (code "37") (name "Net-(LPA2-C)") (class "Default")
      (node (ref "LPA2") (pin "K") (pinfunction "C_K") (pintype "passive"))
      (node (ref "R33") (pin "1") (pinfunction "1_1") (pintype "passive"))
    )
    (net (code "38") (name "Net-(LPB0-C)") (class "Default")
      (node (ref "LPB0") (pin "K") (pinfunction "C_K") (pintype "passive"))
      (node (ref "RCPB0") (pin "1") (pinfunction "1_1") (pintype "passive"))
    )
    (net (code "39") (name "Net-(LPB1-C)") (class "Default")
      (node (ref "LPB1") (pin "K") (pinfunction "C_K") (pintype "passive"))
      (node (ref "RCPB1") (pin "1") (pinfunction "1_1") (pintype "passive"))
    )
    (net (code "40") (name "Net-(LPB2-C)") (class "Default")
      (node (ref "LPB2") (pin "K") (pinfunction "C_K") (pintype "passive"))
      (node (ref "RCPB2") (pin "1") (pinfunction "1_1") (pintype "passive"))
    )
    (net (code "41") (name "Net-(LPB3-C)") (class "Default")
      (node (ref "LPB3") (pin "K") (pinfunction "C_K") (pintype "passive"))
      (node (ref "RCPB3") (pin "1") (pinfunction "1_1") (pintype "passive"))
    )
    (net (code "42") (name "Net-(LPB4-C)") (class "Default")
      (node (ref "LPB4") (pin "K") (pinfunction "C_K") (pintype "passive"))
      (node (ref "RCPB4") (pin "1") (pinfunction "1_1") (pintype "passive"))
    )
    (net (code "43") (name "Net-(LPB5-C)") (class "Default")
      (node (ref "LPB5") (pin "K") (pinfunction "C_K") (pintype "passive"))
      (node (ref "RCPB5") (pin "1") (pinfunction "1_1") (pintype "passive"))
    )
    (net (code "44") (name "Net-(LPD6-C)") (class "Default")
      (node (ref "LPD6") (pin "K") (pinfunction "C_K") (pintype "passive"))
      (node (ref "RCPD6") (pin "1") (pinfunction "1_1") (pintype "passive"))
    )
    (net (code "45") (name "Net-(LPD7-C)") (class "Default")
      (node (ref "LPD7") (pin "K") (pinfunction "C_K") (pintype "passive"))
      (node (ref "RCPD7") (pin "1") (pinfunction "1_1") (pintype "passive"))
    )
    (net (code "46") (name "Net-(Q2-B)") (class "Default")
      (node (ref "Q2") (pin "2") (pinfunction "B_2") (pintype "passive"))
      (node (ref "RBPB1") (pin "1") (pinfunction "1_1") (pintype "passive"))
    )
    (net (code "47") (name "Net-(Q2-C)") (class "Default")
      (node (ref "Q2") (pin "3") (pinfunction "C_3") (pintype "passive"))
      (node (ref "RCPB1") (pin "2") (pinfunction "2_2") (pintype "passive"))
    )
    (net (code "48") (name "Net-(Q3-B)") (class "Default")
      (node (ref "Q3") (pin "2") (pinfunction "B_2") (pintype "passive"))
      (node (ref "RBPB0") (pin "1") (pinfunction "1_1") (pintype "passive"))
    )
    (net (code "49") (name "Net-(Q3-C)") (class "Default")
      (node (ref "Q3") (pin "3") (pinfunction "C_3") (pintype "passive"))
      (node (ref "RCPB0") (pin "2") (pinfunction "2_2") (pintype "passive"))
    )
    (net (code "50") (name "Net-(Q4-B)") (class "Default")
      (node (ref "Q4") (pin "2") (pinfunction "B_2") (pintype "passive"))
      (node (ref "RBPB2") (pin "1") (pinfunction "1_1") (pintype "passive"))
    )
    (net (code "51") (name "Net-(Q4-C)") (class "Default")
      (node (ref "Q4") (pin "3") (pinfunction "C_3") (pintype "passive"))
      (node (ref "RCPB2") (pin "2") (pinfunction "2_2") (pintype "passive"))
    )
    (net (code "52") (name "Net-(Q5-B)") (class "Default")
      (node (ref "Q5") (pin "2") (pinfunction "B_2") (pintype "passive"))
      (node (ref "RBPB3") (pin "1") (pinfunction "1_1") (pintype "passive"))
    )
    (net (code "53") (name "Net-(Q5-C)") (class "Default")
      (node (ref "Q5") (pin "3") (pinfunction "C_3") (pintype "passive"))
      (node (ref "RCPB3") (pin "2") (pinfunction "2_2") (pintype "passive"))
    )
    (net (code "54") (name "Net-(Q6-B)") (class "Default")
      (node (ref "Q6") (pin "2") (pinfunction "B_2") (pintype "passive"))
      (node (ref "RBPB4") (pin "1") (pinfunction "1_1") (pintype "passive"))
    )
    (net (code "55") (name "Net-(Q6-C)") (class "Default")
      (node (ref "Q6") (pin "3") (pinfunction "C_3") (pintype "passive"))
      (node (ref "RCPB4") (pin "2") (pinfunction "2_2") (pintype "passive"))
    )
    (net (code "56") (name "Net-(Q7-B)") (class "Default")
      (node (ref "Q7") (pin "2") (pinfunction "B_2") (pintype "passive"))
      (node (ref "RBPB5") (pin "1") (pinfunction "1_1") (pintype "passive"))
    )
    (net (code "57") (name "Net-(Q7-C)") (class "Default")
      (node (ref "Q7") (pin "3") (pinfunction "C_3") (pintype "passive"))
      (node (ref "RCPB5") (pin "2") (pinfunction "2_2") (pintype "passive"))
    )
    (net (code "58") (name "Net-(Q8-B)") (class "Default")
      (node (ref "Q8") (pin "2") (pinfunction "B_2") (pintype "passive"))
      (node (ref "RBPD6") (pin "1") (pinfunction "1_1") (pintype "passive"))
    )
    (net (code "59") (name "Net-(Q8-C)") (class "Default")
      (node (ref "Q8") (pin "3") (pinfunction "C_3") (pintype "passive"))
      (node (ref "RCPD6") (pin "2") (pinfunction "2_2") (pintype "passive"))
    )
    (net (code "60") (name "Net-(Q9-B)") (class "Default")
      (node (ref "Q9") (pin "2") (pinfunction "B_2") (pintype "passive"))
      (node (ref "RBPD7") (pin "1") (pinfunction "1_1") (pintype "passive"))
    )
    (net (code "61") (name "Net-(Q9-C)") (class "Default")
      (node (ref "Q9") (pin "3") (pinfunction "C_3") (pintype "passive"))
      (node (ref "RCPD7") (pin "2") (pinfunction "2_2") (pintype "passive"))
    )
    (net (code "62") (name "Net-(Q10-B)") (class "Default")
      (node (ref "Q10") (pin "2") (pinfunction "B_2") (pintype "passive"))
      (node (ref "R29") (pin "1") (pinfunction "1_1") (pintype "passive"))
    )
    (net (code "63") (name "Net-(Q10-C)") (class "Default")
      (node (ref "Q10") (pin "3") (pinfunction "C_3") (pintype "passive"))
      (node (ref "R28") (pin "2") (pinfunction "2_2") (pintype "passive"))
    )
    (net (code "64") (name "Net-(Q11-B)") (class "Default")
      (node (ref "Q11") (pin "2") (pinfunction "B_2") (pintype "passive"))
      (node (ref "R32") (pin "1") (pinfunction "1_1") (pintype "passive"))
    )
    (net (code "65") (name "Net-(Q11-C)") (class "Default")
      (node (ref "Q11") (pin "3") (pinfunction "C_3") (pintype "passive"))
      (node (ref "R31") (pin "2") (pinfunction "2_2") (pintype "passive"))
    )
    (net (code "66") (name "Net-(Q12-B)") (class "Default")
      (node (ref "Q12") (pin "2") (pinfunction "B_2") (pintype "passive"))
      (node (ref "R34") (pin "1") (pinfunction "1_1") (pintype "passive"))
    )
    (net (code "67") (name "Net-(Q12-C)") (class "Default")
      (node (ref "Q12") (pin "3") (pinfunction "C_3") (pintype "passive"))
      (node (ref "R33") (pin "2") (pinfunction "2_2") (pintype "passive"))
    )
    (net (code "68") (name "Net-(Q13-B)") (class "Default")
      (node (ref "Q13") (pin "2") (pinfunction "B_2") (pintype "passive"))
      (node (ref "R36") (pin "1") (pinfunction "1_1") (pintype "passive"))
    )
    (net (code "69") (name "Net-(Q13-C)") (class "Default")
      (node (ref "Q13") (pin "3") (pinfunction "C_3") (pintype "passive"))
      (node (ref "R35") (pin "2") (pinfunction "2_2") (pintype "passive"))
    )
    (net (code "70") (name "Net-(U$1A-A)") (class "Default")
      (node (ref "D4") (pin "C") (pinfunction "C_C") (pintype "passive"))
      (node (ref "R6") (pin "2") (pinfunction "2_2") (pintype "passive"))
      (node (ref "U$1") (pin "6") (pinfunction "A_6") (pintype "passive"))
      (node (ref "U$2") (pin "7") (pinfunction "B_7") (pintype "passive"))
      (node (ref "X2") (pin "2") (pinfunction "KL_2") (pintype "passive"))
    )
    (net (code "71") (name "Net-(U$1A-B)") (class "Default")
      (node (ref "D3") (pin "C") (pinfunction "C_C") (pintype "passive"))
      (node (ref "JP1") (pin "1") (pinfunction "1_1") (pintype "passive"))
      (node (ref "U$1") (pin "7") (pinfunction "B_7") (pintype "passive"))
      (node (ref "U$2") (pin "6") (pinfunction "A_6") (pintype "passive"))
      (node (ref "X2") (pin "1") (pinfunction "KL_1") (pintype "passive"))
    )
    (net (code "72") (name "Net-(X1B-KL)") (class "Default")
      (node (ref "R30") (pin "1") (pinfunction "1_1") (pintype "passive"))
      (node (ref "X1") (pin "2") (pinfunction "KL_2") (pintype "passive"))
    )
    (net (code "73") (name "Net-(X3B-KL)") (class "Default")
      (node (ref "R37") (pin "1") (pinfunction "1_1") (pintype "passive"))
      (node (ref "X3") (pin "2") (pinfunction "KL_2") (pintype "passive"))
    )
    (net (code "74") (name "Net-(X5A-KL)") (class "Default")
      (node (ref "D6") (pin "A") (pinfunction "A_A") (pintype "passive"))
      (node (ref "X5") (pin "1") (pinfunction "KL_1") (pintype "passive"))
    )
    (net (code "75") (name "PE") (class "Default")
      (node (ref "R1") (pin "1") (pinfunction "1_1") (pintype "passive"))
      (node (ref "X2") (pin "4") (pinfunction "KL_4") (pintype "passive"))
    )
    (net (code "76") (name "RESET") (class "Default")
      (node (ref "C8") (pin "1") (pinfunction "1_1") (pintype "passive"))
      (node (ref "IC3") (pin "1") (pinfunction "PC6(/RESET)_1") (pintype "bidirectional"))
      (node (ref "JP2") (pin "5") (pinfunction "5_5") (pintype "passive"))
      (node (ref "R7") (pin "2") (pinfunction "2_2") (pintype "passive"))
      (node (ref "S1") (pin "1") (pinfunction "1_1") (pintype "passive"))
      (node (ref "S1") (pin "2") (pinfunction "2_2") (pintype "passive"))
    )
    (net (code "77") (name "VCC") (class "Default")
      (node (ref "C1") (pin "1") (pinfunction "1_1") (pintype "passive"))
      (node (ref "C10") (pin "+") (pinfunction "+_+") (pintype "passive"))
      (node (ref "C2") (pin "1") (pinfunction "1_1") (pintype "passive"))
      (node (ref "C3") (pin "1") (pinfunction "1_1") (pintype "passive"))
      (node (ref "C7") (pin "1") (pinfunction "1_1") (pintype "passive"))
      (node (ref "C9") (pin "1") (pinfunction "1_1") (pintype "passive"))
      (node (ref "IC1") (pin "14") (pinfunction "VCC_14") (pintype "power_in"))
      (node (ref "IC3") (pin "7") (pinfunction "VCC_7") (pintype "power_in"))
      (node (ref "IC7") (pin "3") (pinfunction "VO_3") (pintype "passive"))
      (node (ref "JP3") (pin "4") (pinfunction "4_4") (pintype "passive"))
      (node (ref "JP4") (pin "4") (pinfunction "4_4") (pintype "passive"))
      (node (ref "JP5") (pin "4") (pinfunction "4_4") (pintype "passive"))
      (node (ref "JP7") (pin "1") (pinfunction "1_1") (pintype "passive"))
      (node (ref "JP7") (pin "2") (pinfunction "2_2") (pintype "passive"))
      (node (ref "L1") (pin "2") (pinfunction "2_2") (pintype "passive"))
      (node (ref "LED1") (pin "A") (pinfunction "A_A") (pintype "passive"))
      (node (ref "LED15") (pin "A") (pinfunction "A_A") (pintype "passive"))
      (node (ref "LED2") (pin "K") (pinfunction "C_K") (pintype "passive"))
      (node (ref "LED3") (pin "K") (pinfunction "C_K") (pintype "passive"))
      (node (ref "LPA0") (pin "A") (pinfunction "A_A") (pintype "passive"))
      (node (ref "LPA1") (pin "A") (pinfunction "A_A") (pintype "passive"))
      (node (ref "LPA2") (pin "A") (pinfunction "A_A") (pintype "passive"))
      (node (ref "LPB0") (pin "A") (pinfunction "A_A") (pintype "passive"))
      (node (ref "LPB1") (pin "A") (pinfunction "A_A") (pintype "passive"))
      (node (ref "LPB2") (pin "A") (pinfunction "A_A") (pintype "passive"))
      (node (ref "LPB3") (pin "A") (pinfunction "A_A") (pintype "passive"))
      (node (ref "LPB4") (pin "A") (pinfunction "A_A") (pintype "passive"))
      (node (ref "LPB5") (pin "A") (pinfunction "A_A") (pintype "passive"))
      (node (ref "LPD6") (pin "A") (pinfunction "A_A") (pintype "passive"))
      (node (ref "LPD7") (pin "A") (pinfunction "A_A") (pintype "passive"))
      (node (ref "R2") (pin "1") (pinfunction "1_1") (pintype "passive"))
      (node (ref "R4") (pin "1") (pinfunction "1_1") (pintype "passive"))
      (node (ref "R7") (pin "1") (pinfunction "1_1") (pintype "passive"))
      (node (ref "U$1") (pin "8") (pinfunction "VCC_8") (pintype "power_in"))
      (node (ref "U$2") (pin "8") (pinfunction "VCC_8") (pintype "power_in"))
      (node (ref "X1") (pin "3") (pinfunction "KL_3") (pintype "passive"))
      (node (ref "X3") (pin "3") (pinfunction "KL_3") (pintype "passive"))
    )
    (net (code "78") (name "XTAL1") (class "Default")
      (node (ref "C5") (pin "1") (pinfunction "1_1") (pintype "passive"))
      (node (ref "IC3") (pin "9") (pinfunction "PB6(XTAL1/TOSC1)_9") (pintype "bidirectional"))
      (node (ref "Q1") (pin "1") (pinfunction "1_1") (pintype "passive"))
    )
    (net (code "79") (name "XTAL2") (class "Default")
      (node (ref "C6") (pin "1") (pinfunction "1_1") (pintype "passive"))
      (node (ref "IC3") (pin "10") (pinfunction "PB7(XTAL2/TOSC2)_10") (pintype "bidirectional"))
      (node (ref "Q1") (pin "2") (pinfunction "2_2") (pintype "passive"))
    )
    (net (code "80") (name "unconnected-(IC2-OPT-Pad3)") (class "Default")
      (node (ref "IC2") (pin "3") (pinfunction "OPT_3") (pintype "output"))
    )
    (net (code "81") (name "unconnected-(JP2-Pad2)") (class "Default")
      (node (ref "JP2") (pin "2") (pinfunction "2_2") (pintype "passive"))
    )
    (net (code "82") (name "unconnected-(JP2-Pad3)") (class "Default")
      (node (ref "JP2") (pin "3") (pinfunction "3_3") (pintype "passive"))
    )
    (net (code "83") (name "unconnected-(U$2A-DI-Pad4)") (class "Default")
      (node (ref "U$2") (pin "4") (pinfunction "DI_4") (pintype "input"))
    )
  )
)
